# Temp_Sense.net
KiCad netlist of a schematic drawn in Altium Designer
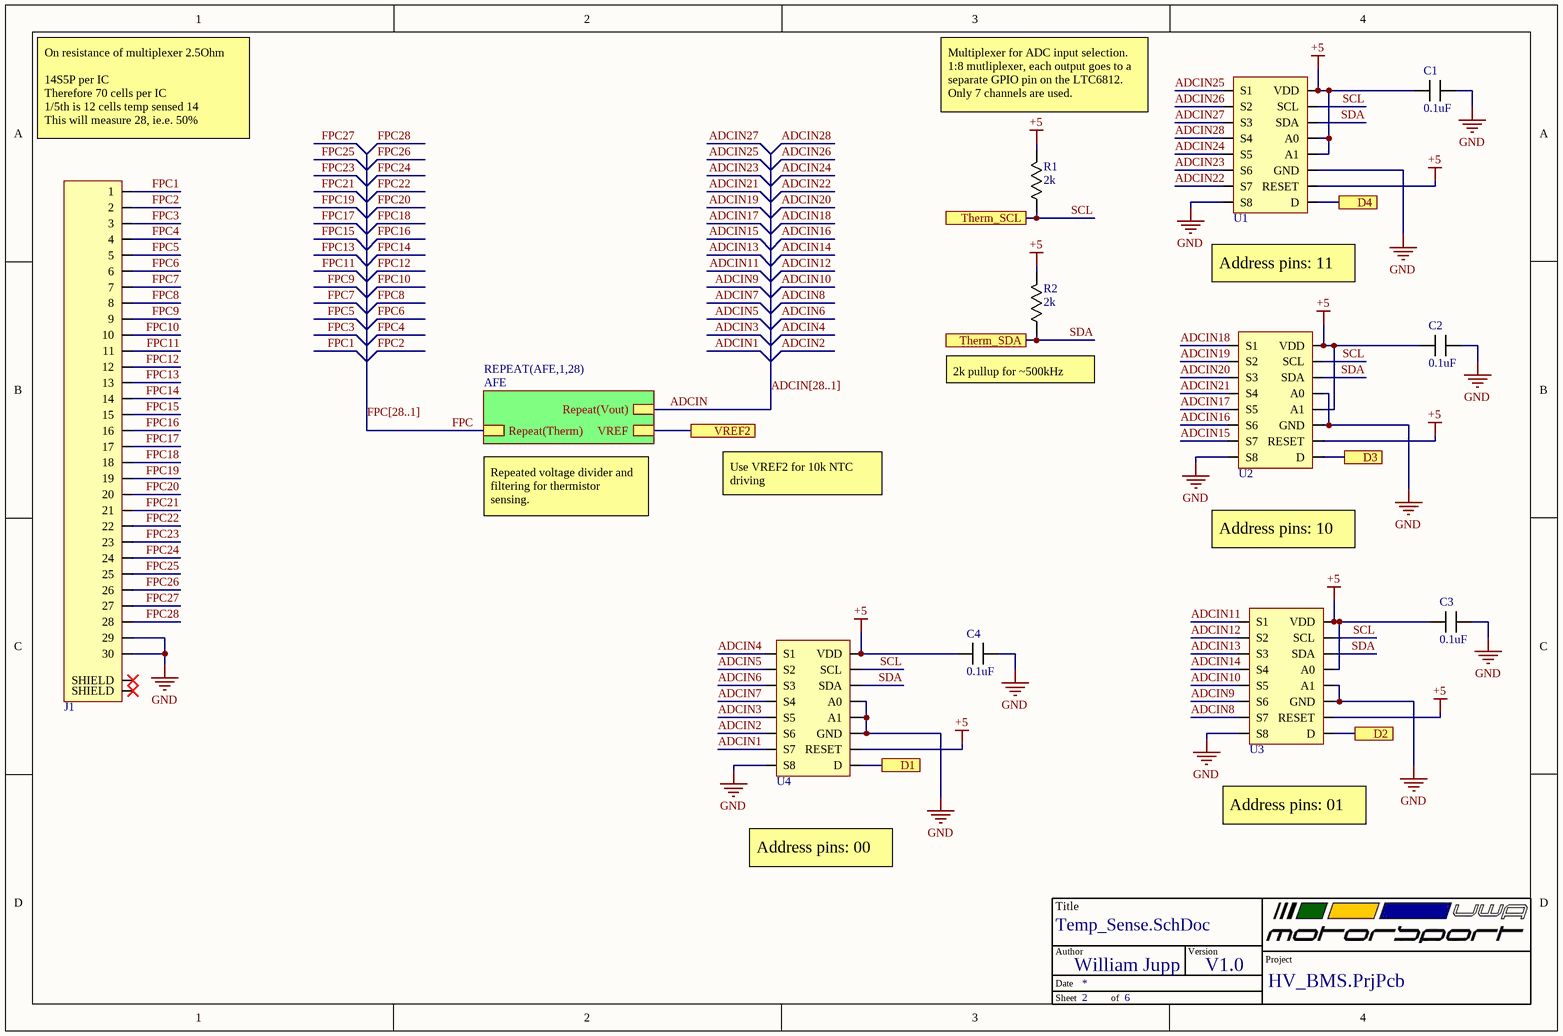
[diagram p0: Temp_Sense.SchDoc]

(export (version "E")
  (design (tool "Eeschema 10.0.6"))
  (components
    (comp (ref "C1")
      (value "0.1uF")
      (footprint "C_0603")
      (description "Capacitor")
      (fields (field (name "Comment") "C"))
      (libsource (lib "Passives") (part "Capacitor"))
    )
    (comp (ref "C2")
      (value "0.1uF")
      (footprint "C_0603")
      (description "Capacitor")
      (fields (field (name "Comment") "C"))
      (libsource (lib "Passives") (part "Capacitor"))
    )
    (comp (ref "C3")
      (value "0.1uF")
      (footprint "C_0603")
      (description "Capacitor")
      (fields (field (name "Comment") "C"))
      (libsource (lib "Passives") (part "Capacitor"))
    )
    (comp (ref "C4")
      (value "0.1uF")
      (footprint "C_0603")
      (description "Capacitor")
      (fields (field (name "Comment") "C"))
      (libsource (lib "Passives") (part "Capacitor"))
    )
    (comp (ref "J1")
      (value "3-84953-0")
      (footprint "3-84953-0")
      (description "CONN FPC TOP 30POS 1.00MM R/A")
      (fields (field (name "MANUFACTURER") "TE Connectivity"))
      (libsource (lib "TE_Con") (part "3-84953-0"))
    )
    (comp (ref "R1")
      (value "2k")
      (footprint "R-0603")
      (description "Resistor")
      (libsource (lib "Passives") (part "Resistor"))
    )
    (comp (ref "R2")
      (value "2k")
      (footprint "R-0603")
      (description "Resistor")
      (libsource (lib "Passives") (part "Resistor"))
    )
    (comp (ref "U1")
      (value "ADG728")
      (footprint "ADG728")
      (description "Analog Multiplexer Single 8:1 16-Pin TSSOP Tube")
      (fields
        (field (name "MANUFACTURER") "Analog Devices")
        (field (name "MANUFACTURER PART NUMBER") "ADG728BRUZ")
      )
      (libsource (lib "HV_BMS_SCH_LIB") (part "ADG728"))
    )
    (comp (ref "U2")
      (value "ADG728")
      (footprint "ADG728")
      (description "Analog Multiplexer Single 8:1 16-Pin TSSOP Tube")
      (fields
        (field (name "MANUFACTURER") "Analog Devices")
        (field (name "MANUFACTURER PART NUMBER") "ADG728BRUZ")
      )
      (libsource (lib "HV_BMS_SCH_LIB") (part "ADG728"))
    )
    (comp (ref "U3")
      (value "ADG728")
      (footprint "ADG728")
      (description "Analog Multiplexer Single 8:1 16-Pin TSSOP Tube")
      (fields
        (field (name "MANUFACTURER") "Analog Devices")
        (field (name "MANUFACTURER PART NUMBER") "ADG728BRUZ")
      )
      (libsource (lib "HV_BMS_SCH_LIB") (part "ADG728"))
    )
    (comp (ref "U4")
      (value "ADG728")
      (footprint "ADG728")
      (description "Analog Multiplexer Single 8:1 16-Pin TSSOP Tube")
      (fields
        (field (name "MANUFACTURER") "Analog Devices")
        (field (name "MANUFACTURER PART NUMBER") "ADG728BRUZ")
      )
      (libsource (lib "HV_BMS_SCH_LIB") (part "ADG728"))
    )
  )
  (nets
    (net (code "1") (name "+5") (class "Default")
      (node (ref "C1") (pin "2") (pinfunction "2_2") (pintype "passive"))
      (node (ref "C2") (pin "2") (pinfunction "2_2") (pintype "passive"))
      (node (ref "C3") (pin "2") (pinfunction "2_2") (pintype "passive"))
      (node (ref "C4") (pin "2") (pinfunction "2_2") (pintype "passive"))
      (node (ref "R1") (pin "2") (pinfunction "2_2") (pintype "passive"))
      (node (ref "R2") (pin "2") (pinfunction "2_2") (pintype "passive"))
      (node (ref "U1") (pin "13") (pinfunction "VDD_13") (pintype "passive"))
      (node (ref "U1") (pin "15") (pinfunction "A1_15") (pintype "passive"))
      (node (ref "U1") (pin "16") (pinfunction "A0_16") (pintype "passive"))
      (node (ref "U1") (pin "2") (pinfunction "RESET_2") (pintype "passive"))
      (node (ref "U2") (pin "13") (pinfunction "VDD_13") (pintype "passive"))
      (node (ref "U2") (pin "15") (pinfunction "A1_15") (pintype "passive"))
      (node (ref "U2") (pin "2") (pinfunction "RESET_2") (pintype "passive"))
      (node (ref "U3") (pin "13") (pinfunction "VDD_13") (pintype "passive"))
      (node (ref "U3") (pin "16") (pinfunction "A0_16") (pintype "passive"))
      (node (ref "U3") (pin "2") (pinfunction "RESET_2") (pintype "passive"))
      (node (ref "U4") (pin "13") (pinfunction "VDD_13") (pintype "passive"))
      (node (ref "U4") (pin "2") (pinfunction "RESET_2") (pintype "passive"))
    )
    (net (code "3") (name "/ADCIN1") (class "Default")
      (node (ref "U4") (pin "10") (pinfunction "S7_10") (pintype "passive"))
    )
    (net (code "4") (name "/ADCIN2") (class "Default")
      (node (ref "U4") (pin "11") (pinfunction "S6_11") (pintype "passive"))
    )
    (net (code "5") (name "/ADCIN3") (class "Default")
      (node (ref "U4") (pin "12") (pinfunction "S5_12") (pintype "passive"))
    )
    (net (code "6") (name "/ADCIN4") (class "Default")
      (node (ref "U4") (pin "4") (pinfunction "S1_4") (pintype "passive"))
    )
    (net (code "7") (name "/ADCIN5") (class "Default")
      (node (ref "U4") (pin "5") (pinfunction "S2_5") (pintype "passive"))
    )
    (net (code "8") (name "/ADCIN6") (class "Default")
      (node (ref "U4") (pin "6") (pinfunction "S3_6") (pintype "passive"))
    )
    (net (code "9") (name "/ADCIN7") (class "Default")
      (node (ref "U4") (pin "7") (pinfunction "S4_7") (pintype "passive"))
    )
    (net (code "10") (name "/ADCIN8") (class "Default")
      (node (ref "U3") (pin "10") (pinfunction "S7_10") (pintype "passive"))
    )
    (net (code "11") (name "/ADCIN9") (class "Default")
      (node (ref "U3") (pin "11") (pinfunction "S6_11") (pintype "passive"))
    )
    (net (code "12") (name "/ADCIN10") (class "Default")
      (node (ref "U3") (pin "12") (pinfunction "S5_12") (pintype "passive"))
    )
    (net (code "13") (name "/ADCIN11") (class "Default")
      (node (ref "U3") (pin "4") (pinfunction "S1_4") (pintype "passive"))
    )
    (net (code "14") (name "/ADCIN12") (class "Default")
      (node (ref "U3") (pin "5") (pinfunction "S2_5") (pintype "passive"))
    )
    (net (code "15") (name "/ADCIN13") (class "Default")
      (node (ref "U3") (pin "6") (pinfunction "S3_6") (pintype "passive"))
    )
    (net (code "16") (name "/ADCIN14") (class "Default")
      (node (ref "U3") (pin "7") (pinfunction "S4_7") (pintype "passive"))
    )
    (net (code "17") (name "/ADCIN15") (class "Default")
      (node (ref "U2") (pin "10") (pinfunction "S7_10") (pintype "passive"))
    )
    (net (code "18") (name "/ADCIN16") (class "Default")
      (node (ref "U2") (pin "11") (pinfunction "S6_11") (pintype "passive"))
    )
    (net (code "19") (name "/ADCIN17") (class "Default")
      (node (ref "U2") (pin "12") (pinfunction "S5_12") (pintype "passive"))
    )
    (net (code "20") (name "/ADCIN18") (class "Default")
      (node (ref "U2") (pin "4") (pinfunction "S1_4") (pintype "passive"))
    )
    (net (code "21") (name "/ADCIN19") (class "Default")
      (node (ref "U2") (pin "5") (pinfunction "S2_5") (pintype "passive"))
    )
    (net (code "22") (name "/ADCIN20") (class "Default")
      (node (ref "U2") (pin "6") (pinfunction "S3_6") (pintype "passive"))
    )
    (net (code "23") (name "/ADCIN21") (class "Default")
      (node (ref "U2") (pin "7") (pinfunction "S4_7") (pintype "passive"))
    )
    (net (code "24") (name "/ADCIN22") (class "Default")
      (node (ref "U1") (pin "10") (pinfunction "S7_10") (pintype "passive"))
    )
    (net (code "25") (name "/ADCIN23") (class "Default")
      (node (ref "U1") (pin "11") (pinfunction "S6_11") (pintype "passive"))
    )
    (net (code "26") (name "/ADCIN24") (class "Default")
      (node (ref "U1") (pin "12") (pinfunction "S5_12") (pintype "passive"))
    )
    (net (code "27") (name "/ADCIN25") (class "Default")
      (node (ref "U1") (pin "4") (pinfunction "S1_4") (pintype "passive"))
    )
    (net (code "28") (name "/ADCIN26") (class "Default")
      (node (ref "U1") (pin "5") (pinfunction "S2_5") (pintype "passive"))
    )
    (net (code "29") (name "/ADCIN27") (class "Default")
      (node (ref "U1") (pin "6") (pinfunction "S3_6") (pintype "passive"))
    )
    (net (code "30") (name "/ADCIN28") (class "Default")
      (node (ref "U1") (pin "7") (pinfunction "S4_7") (pintype "passive"))
    )
    (net (code "32") (name "/D1") (class "Default")
      (node (ref "U4") (pin "8") (pinfunction "D_8") (pintype "passive"))
    )
    (net (code "33") (name "/D2") (class "Default")
      (node (ref "U3") (pin "8") (pinfunction "D_8") (pintype "passive"))
    )
    (net (code "34") (name "/D3") (class "Default")
      (node (ref "U2") (pin "8") (pinfunction "D_8") (pintype "passive"))
    )
    (net (code "35") (name "/D4") (class "Default")
      (node (ref "U1") (pin "8") (pinfunction "D_8") (pintype "passive"))
    )
    (net (code "37") (name "/FPC1") (class "Default")
      (node (ref "J1") (pin "1") (pinfunction "1_1") (pintype "passive"))
    )
    (net (code "38") (name "/FPC2") (class "Default")
      (node (ref "J1") (pin "2") (pinfunction "2_2") (pintype "passive"))
    )
    (net (code "39") (name "/FPC3") (class "Default")
      (node (ref "J1") (pin "3") (pinfunction "3_3") (pintype "passive"))
    )
    (net (code "40") (name "/FPC4") (class "Default")
      (node (ref "J1") (pin "4") (pinfunction "4_4") (pintype "passive"))
    )
    (net (code "41") (name "/FPC5") (class "Default")
      (node (ref "J1") (pin "5") (pinfunction "5_5") (pintype "passive"))
    )
    (net (code "42") (name "/FPC6") (class "Default")
      (node (ref "J1") (pin "6") (pinfunction "6_6") (pintype "passive"))
    )
    (net (code "43") (name "/FPC7") (class "Default")
      (node (ref "J1") (pin "7") (pinfunction "7_7") (pintype "passive"))
    )
    (net (code "44") (name "/FPC8") (class "Default")
      (node (ref "J1") (pin "8") (pinfunction "8_8") (pintype "passive"))
    )
    (net (code "45") (name "/FPC9") (class "Default")
      (node (ref "J1") (pin "9") (pinfunction "9_9") (pintype "passive"))
    )
    (net (code "46") (name "/FPC10") (class "Default")
      (node (ref "J1") (pin "10") (pinfunction "10_10") (pintype "passive"))
    )
    (net (code "47") (name "/FPC11") (class "Default")
      (node (ref "J1") (pin "11") (pinfunction "11_11") (pintype "passive"))
    )
    (net (code "48") (name "/FPC12") (class "Default")
      (node (ref "J1") (pin "12") (pinfunction "12_12") (pintype "passive"))
    )
    (net (code "49") (name "/FPC13") (class "Default")
      (node (ref "J1") (pin "13") (pinfunction "13_13") (pintype "passive"))
    )
    (net (code "50") (name "/FPC14") (class "Default")
      (node (ref "J1") (pin "14") (pinfunction "14_14") (pintype "passive"))
    )
    (net (code "51") (name "/FPC15") (class "Default")
      (node (ref "J1") (pin "15") (pinfunction "15_15") (pintype "passive"))
    )
    (net (code "52") (name "/FPC16") (class "Default")
      (node (ref "J1") (pin "16") (pinfunction "16_16") (pintype "passive"))
    )
    (net (code "53") (name "/FPC17") (class "Default")
      (node (ref "J1") (pin "17") (pinfunction "17_17") (pintype "passive"))
    )
    (net (code "54") (name "/FPC18") (class "Default")
      (node (ref "J1") (pin "18") (pinfunction "18_18") (pintype "passive"))
    )
    (net (code "55") (name "/FPC19") (class "Default")
      (node (ref "J1") (pin "19") (pinfunction "19_19") (pintype "passive"))
    )
    (net (code "56") (name "/FPC20") (class "Default")
      (node (ref "J1") (pin "20") (pinfunction "20_20") (pintype "passive"))
    )
    (net (code "57") (name "/FPC21") (class "Default")
      (node (ref "J1") (pin "21") (pinfunction "21_21") (pintype "passive"))
    )
    (net (code "58") (name "/FPC22") (class "Default")
      (node (ref "J1") (pin "22") (pinfunction "22_22") (pintype "passive"))
    )
    (net (code "59") (name "/FPC23") (class "Default")
      (node (ref "J1") (pin "23") (pinfunction "23_23") (pintype "passive"))
    )
    (net (code "60") (name "/FPC24") (class "Default")
      (node (ref "J1") (pin "24") (pinfunction "24_24") (pintype "passive"))
    )
    (net (code "61") (name "/FPC25") (class "Default")
      (node (ref "J1") (pin "25") (pinfunction "25_25") (pintype "passive"))
    )
    (net (code "62") (name "/FPC26") (class "Default")
      (node (ref "J1") (pin "26") (pinfunction "26_26") (pintype "passive"))
    )
    (net (code "63") (name "/FPC27") (class "Default")
      (node (ref "J1") (pin "27") (pinfunction "27_27") (pintype "passive"))
    )
    (net (code "64") (name "/FPC28") (class "Default")
      (node (ref "J1") (pin "28") (pinfunction "28_28") (pintype "passive"))
    )
    (net (code "66") (name "/SCL") (class "Default")
      (node (ref "R1") (pin "1") (pinfunction "1_1") (pintype "passive"))
      (node (ref "U1") (pin "1") (pinfunction "SCL_1") (pintype "passive"))
      (node (ref "U2") (pin "1") (pinfunction "SCL_1") (pintype "passive"))
      (node (ref "U3") (pin "1") (pinfunction "SCL_1") (pintype "passive"))
      (node (ref "U4") (pin "1") (pinfunction "SCL_1") (pintype "passive"))
    )
    (net (code "67") (name "/SDA") (class "Default")
      (node (ref "R2") (pin "1") (pinfunction "1_1") (pintype "passive"))
      (node (ref "U1") (pin "3") (pinfunction "SDA_3") (pintype "passive"))
      (node (ref "U2") (pin "3") (pinfunction "SDA_3") (pintype "passive"))
      (node (ref "U3") (pin "3") (pinfunction "SDA_3") (pintype "passive"))
      (node (ref "U4") (pin "3") (pinfunction "SDA_3") (pintype "passive"))
    )
    (net (code "69") (name "GND") (class "Default")
      (node (ref "C1") (pin "1") (pinfunction "1_1") (pintype "passive"))
      (node (ref "C2") (pin "1") (pinfunction "1_1") (pintype "passive"))
      (node (ref "C3") (pin "1") (pinfunction "1_1") (pintype "passive"))
      (node (ref "C4") (pin "1") (pinfunction "1_1") (pintype "passive"))
      (node (ref "J1") (pin "29") (pinfunction "29_29") (pintype "passive"))
      (node (ref "J1") (pin "30") (pinfunction "30_30") (pintype "passive"))
      (node (ref "U1") (pin "14") (pinfunction "GND_14") (pintype "passive"))
      (node (ref "U1") (pin "9") (pinfunction "S8_9") (pintype "passive"))
      (node (ref "U2") (pin "14") (pinfunction "GND_14") (pintype "passive"))
      (node (ref "U2") (pin "16") (pinfunction "A0_16") (pintype "passive"))
      (node (ref "U2") (pin "9") (pinfunction "S8_9") (pintype "passive"))
      (node (ref "U3") (pin "14") (pinfunction "GND_14") (pintype "passive"))
      (node (ref "U3") (pin "15") (pinfunction "A1_15") (pintype "passive"))
      (node (ref "U3") (pin "9") (pinfunction "S8_9") (pintype "passive"))
      (node (ref "U4") (pin "14") (pinfunction "GND_14") (pintype "passive"))
      (node (ref "U4") (pin "15") (pinfunction "A1_15") (pintype "passive"))
      (node (ref "U4") (pin "16") (pinfunction "A0_16") (pintype "passive"))
      (node (ref "U4") (pin "9") (pinfunction "S8_9") (pintype "passive"))
    )
    (net (code "70") (name "unconnected-(J1-SHIELD-PadS1)") (class "Default")
      (node (ref "J1") (pin "S1") (pinfunction "SHIELD_S1") (pintype "passive+no_connect"))
    )
    (net (code "71") (name "unconnected-(J1-SHIELD-PadS2)") (class "Default")
      (node (ref "J1") (pin "S2") (pinfunction "SHIELD_S2") (pintype "passive+no_connect"))
    )
  )
)
